# PLC-_-_-V3.net
KiCad netlist of a schematic drawn in Altium Designer
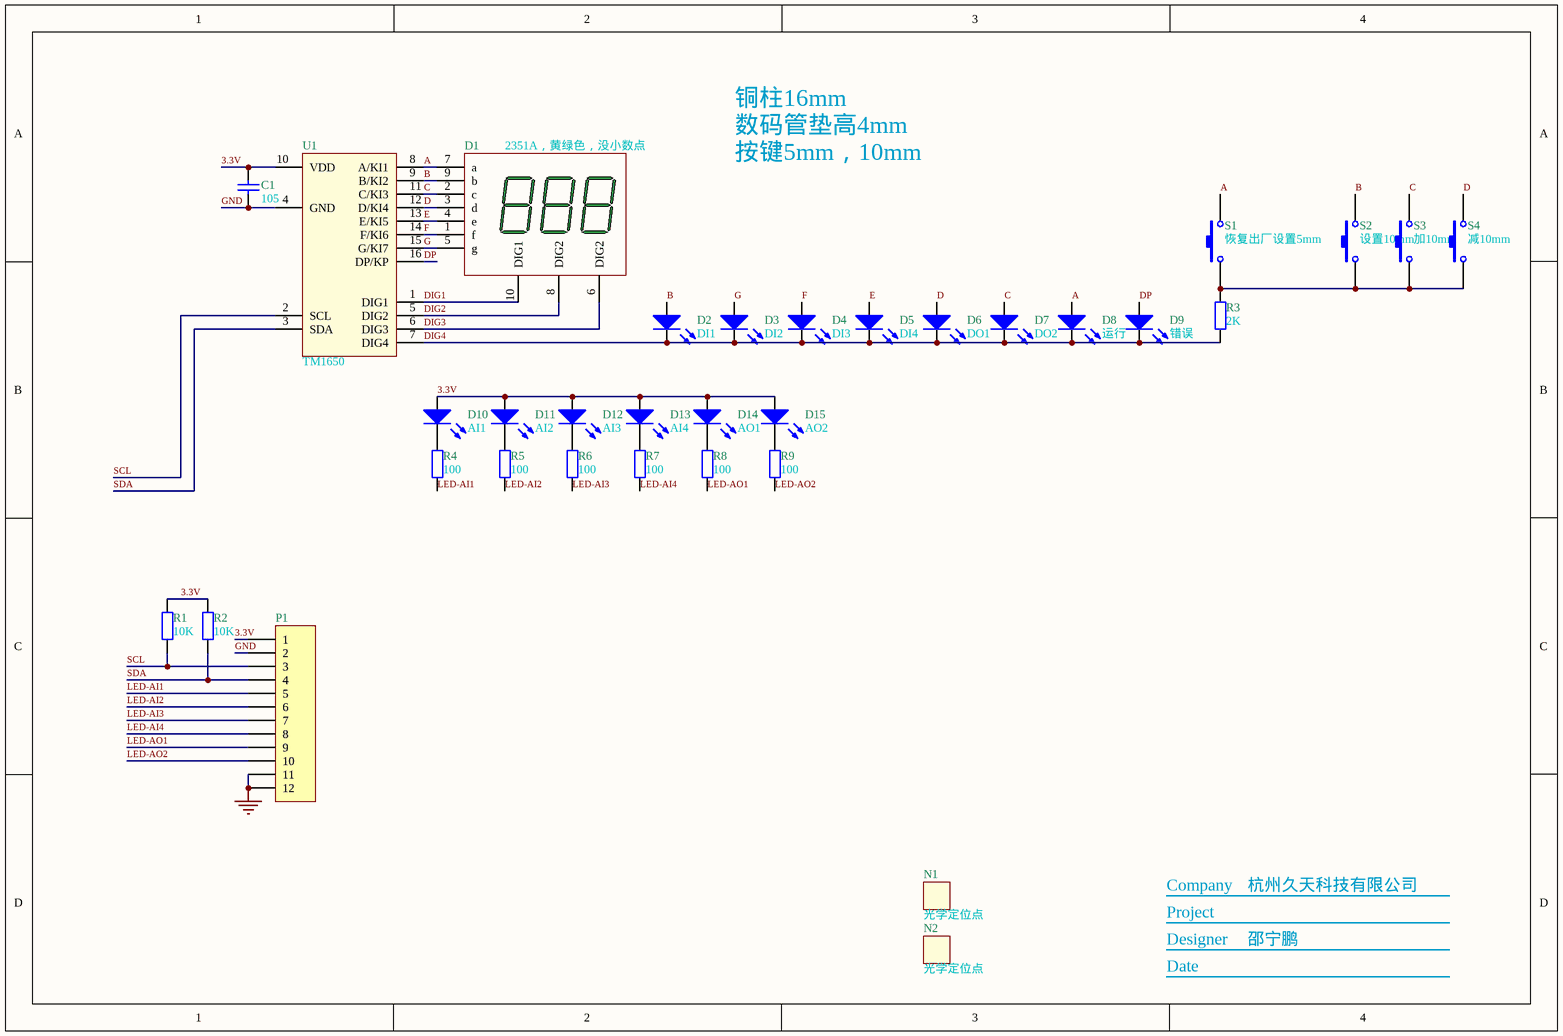
[diagram p0: PLC-无线通讯版-显示板-V3.SchDoc]

(export (version "E")
  (design (tool "Eeschema 10.0.6"))
  (components
    (comp (ref "C1")
      (value "105")
      (footprint "C-0603")
      (description "Capacitor")
      (fields (field (name "PUBLISHER") "Altium Limited"))
      (libsource (lib "元件2.0") (part "Cap"))
    )
    (comp (ref "D1")
      (value "2351A，黄绿色，没小数点")
      (footprint "3位0.25英寸")
      (libsource (lib "7显示屏-V1.0") (part "3位数码管-无点-2351A"))
    )
    (comp (ref "D2")
      (value "DI1")
      (footprint "LED-0603-GREEN")
      (fields (field (name "PUBLISHER") "Altium Limited"))
      (libsource (lib "4二极管-V1.1") (part "LED-0603-Blue"))
    )
    (comp (ref "D3")
      (value "DI2")
      (footprint "LED-0603-GREEN")
      (fields (field (name "PUBLISHER") "Altium Limited"))
      (libsource (lib "4二极管-V1.1") (part "LED-0603-Blue"))
    )
    (comp (ref "D4")
      (value "DI3")
      (footprint "LED-0603-GREEN")
      (fields (field (name "PUBLISHER") "Altium Limited"))
      (libsource (lib "4二极管-V1.1") (part "LED-0603-Blue"))
    )
    (comp (ref "D5")
      (value "DI4")
      (footprint "LED-0603-GREEN")
      (fields (field (name "PUBLISHER") "Altium Limited"))
      (libsource (lib "4二极管-V1.1") (part "LED-0603-Blue"))
    )
    (comp (ref "D6")
      (value "DO1")
      (footprint "LED-0603-GREEN")
      (fields (field (name "PUBLISHER") "Altium Limited"))
      (libsource (lib "4二极管-V1.1") (part "LED-0603-Blue"))
    )
    (comp (ref "D7")
      (value "DO2")
      (footprint "LED-0603-GREEN")
      (fields (field (name "PUBLISHER") "Altium Limited"))
      (libsource (lib "4二极管-V1.1") (part "LED-0603-Blue"))
    )
    (comp (ref "D8")
      (value "运行")
      (footprint "LED-0603-Blue")
      (fields (field (name "PUBLISHER") "Altium Limited"))
      (libsource (lib "4二极管-V1.1") (part "LED-0603-Blue"))
    )
    (comp (ref "D9")
      (value "错误")
      (footprint "LED-0603-Red")
      (fields (field (name "PUBLISHER") "Altium Limited"))
      (libsource (lib "4二极管-V1.1") (part "LED-0603-Blue"))
    )
    (comp (ref "D10")
      (value "AI1")
      (footprint "LED-0603-GREEN")
      (fields (field (name "PUBLISHER") "Altium Limited"))
      (libsource (lib "4二极管-V1.1") (part "LED-0603-Blue"))
    )
    (comp (ref "D11")
      (value "AI2")
      (footprint "LED-0603-GREEN")
      (fields (field (name "PUBLISHER") "Altium Limited"))
      (libsource (lib "4二极管-V1.1") (part "LED-0603-Blue"))
    )
    (comp (ref "D12")
      (value "AI3")
      (footprint "LED-0603-GREEN")
      (fields (field (name "PUBLISHER") "Altium Limited"))
      (libsource (lib "4二极管-V1.1") (part "LED-0603-Blue"))
    )
    (comp (ref "D13")
      (value "AI4")
      (footprint "LED-0603-GREEN")
      (fields (field (name "PUBLISHER") "Altium Limited"))
      (libsource (lib "4二极管-V1.1") (part "LED-0603-Blue"))
    )
    (comp (ref "D14")
      (value "AO1")
      (footprint "LED-0603-GREEN")
      (fields (field (name "PUBLISHER") "Altium Limited"))
      (libsource (lib "4二极管-V1.1") (part "LED-0603-Blue"))
    )
    (comp (ref "D15")
      (value "AO2")
      (footprint "LED-0603-GREEN")
      (fields (field (name "PUBLISHER") "Altium Limited"))
      (libsource (lib "4二极管-V1.1") (part "LED-0603-Blue"))
    )
    (comp (ref "N1") (value "光学定位点") (footprint "MARK-1mm-3mm") (libsource (lib "11其他元件-V1.0") (part "无引脚")))
    (comp (ref "N2") (value "光学定位点") (footprint "MARK-1mm-3mm") (libsource (lib "11其他元件-V1.0") (part "无引脚")))
    (comp (ref "P1")
      (value "~")
      (footprint "FPC-1.0mm下接翻盖_10P")
      (description "Header, 12-Pin")
      (fields (field (name "PUBLISHER") "Altium Limited"))
      (libsource (lib "5排针-V1.0") (part "Header 12"))
    )
    (comp (ref "R1")
      (value "10K")
      (footprint "R-0603")
      (description "0603")
      (fields (field (name "PUBLISHER") "Altium Limited"))
      (libsource (lib "") (part "Res2-0603_1"))
    )
    (comp (ref "R2")
      (value "10K")
      (footprint "R-0603")
      (description "0603")
      (fields (field (name "PUBLISHER") "Altium Limited"))
      (libsource (lib "") (part "Res2-0603_1"))
    )
    (comp (ref "R3")
      (value "2K")
      (footprint "R-0603")
      (description "0603")
      (fields (field (name "PUBLISHER") "Altium Limited"))
      (libsource (lib "1电阻-V1.0") (part "Res2-0603"))
    )
    (comp (ref "R4")
      (value "100")
      (footprint "R-0603")
      (description "0603")
      (fields (field (name "PUBLISHER") "Altium Limited"))
      (libsource (lib "1电阻-V1.0") (part "Res2-0603"))
    )
    (comp (ref "R5")
      (value "100")
      (footprint "R-0603")
      (description "0603")
      (fields (field (name "PUBLISHER") "Altium Limited"))
      (libsource (lib "1电阻-V1.0") (part "Res2-0603"))
    )
    (comp (ref "R6")
      (value "100")
      (footprint "R-0603")
      (description "0603")
      (fields (field (name "PUBLISHER") "Altium Limited"))
      (libsource (lib "1电阻-V1.0") (part "Res2-0603"))
    )
    (comp (ref "R7")
      (value "100")
      (footprint "R-0603")
      (description "0603")
      (fields (field (name "PUBLISHER") "Altium Limited"))
      (libsource (lib "1电阻-V1.0") (part "Res2-0603"))
    )
    (comp (ref "R8")
      (value "100")
      (footprint "R-0603")
      (description "0603")
      (fields (field (name "PUBLISHER") "Altium Limited"))
      (libsource (lib "1电阻-V1.0") (part "Res2-0603"))
    )
    (comp (ref "R9")
      (value "100")
      (footprint "R-0603")
      (description "0603")
      (fields (field (name "PUBLISHER") "Altium Limited"))
      (libsource (lib "1电阻-V1.0") (part "Res2-0603"))
    )
    (comp (ref "S1")
      (value "恢复出厂设置5mm")
      (footprint "SB-6*6*9.5_贴片")
      (description "SB-6*6*10")
      (fields (field (name "PUBLISHER") "Altium Limited"))
      (libsource (lib "开关-V1") (part "SB-6*6*9"))
    )
    (comp (ref "S2")
      (value "设置10mm")
      (footprint "SB-6*6*9.5_贴片")
      (description "SB-6*6*10")
      (fields (field (name "PUBLISHER") "Altium Limited"))
      (libsource (lib "开关-V1") (part "SB-6*6*9"))
    )
    (comp (ref "S3")
      (value "加10mm")
      (footprint "SB-6*6*9.5_贴片")
      (description "SB-6*6*10")
      (fields (field (name "PUBLISHER") "Altium Limited"))
      (libsource (lib "开关-V1") (part "SB-6*6*9"))
    )
    (comp (ref "S4")
      (value "减10mm")
      (footprint "SB-6*6*9.5_贴片")
      (description "SB-6*6*10")
      (fields (field (name "PUBLISHER") "Altium Limited"))
      (libsource (lib "开关-V1") (part "SB-6*6*9"))
    )
    (comp (ref "U1")
      (value "TM1650")
      (footprint "SOP-16-M")
      (description "共阴数码管驱动器")
      (libsource (lib "8集成电路-V1.1") (part "TM1650"))
    )
  )
  (nets
    (net (code "1") (name "/3.3V") (class "Default")
      (node (ref "C1") (pin "2") (pinfunction "2_2") (pintype "passive"))
      (node (ref "D10") (pin "1") (pinfunction "A_1") (pintype "passive"))
      (node (ref "D11") (pin "1") (pinfunction "A_1") (pintype "passive"))
      (node (ref "D12") (pin "1") (pinfunction "A_1") (pintype "passive"))
      (node (ref "D13") (pin "1") (pinfunction "A_1") (pintype "passive"))
      (node (ref "D14") (pin "1") (pinfunction "A_1") (pintype "passive"))
      (node (ref "D15") (pin "1") (pinfunction "A_1") (pintype "passive"))
      (node (ref "P1") (pin "1") (pinfunction "1_1") (pintype "passive"))
      (node (ref "R1") (pin "2") (pinfunction "2_2") (pintype "passive"))
      (node (ref "R2") (pin "2") (pinfunction "2_2") (pintype "passive"))
      (node (ref "U1") (pin "10") (pinfunction "VDD_10") (pintype "passive"))
    )
    (net (code "2") (name "/A") (class "Default")
      (node (ref "D1") (pin "7") (pinfunction "a_7") (pintype "passive"))
      (node (ref "D8") (pin "1") (pinfunction "A_1") (pintype "passive"))
      (node (ref "S1") (pin "2") (pinfunction "2_2") (pintype "passive"))
      (node (ref "U1") (pin "8") (pinfunction "A/KI1_8") (pintype "passive"))
    )
    (net (code "3") (name "/B") (class "Default")
      (node (ref "D1") (pin "9") (pinfunction "b_9") (pintype "passive"))
      (node (ref "D2") (pin "1") (pinfunction "A_1") (pintype "passive"))
      (node (ref "S2") (pin "2") (pinfunction "2_2") (pintype "passive"))
      (node (ref "U1") (pin "9") (pinfunction "B/KI2_9") (pintype "passive"))
    )
    (net (code "4") (name "/C") (class "Default")
      (node (ref "D1") (pin "2") (pinfunction "c_2") (pintype "passive"))
      (node (ref "D7") (pin "1") (pinfunction "A_1") (pintype "passive"))
      (node (ref "S3") (pin "2") (pinfunction "2_2") (pintype "passive"))
      (node (ref "U1") (pin "11") (pinfunction "C/KI3_11") (pintype "passive"))
    )
    (net (code "5") (name "/D") (class "Default")
      (node (ref "D1") (pin "3") (pinfunction "d_3") (pintype "passive"))
      (node (ref "D6") (pin "1") (pinfunction "A_1") (pintype "passive"))
      (node (ref "S4") (pin "2") (pinfunction "2_2") (pintype "passive"))
      (node (ref "U1") (pin "12") (pinfunction "D/KI4_12") (pintype "passive"))
    )
    (net (code "6") (name "/DIG1") (class "Default")
      (node (ref "D1") (pin "10") (pinfunction "DIG1_10") (pintype "passive"))
      (node (ref "U1") (pin "1") (pinfunction "DIG1_1") (pintype "passive"))
    )
    (net (code "7") (name "/DIG2") (class "Default")
      (node (ref "D1") (pin "8") (pinfunction "DIG2_8") (pintype "passive"))
      (node (ref "U1") (pin "5") (pinfunction "DIG2_5") (pintype "passive"))
    )
    (net (code "8") (name "/DIG3") (class "Default")
      (node (ref "D1") (pin "6") (pinfunction "DIG2_6") (pintype "passive"))
      (node (ref "U1") (pin "6") (pinfunction "DIG3_6") (pintype "passive"))
    )
    (net (code "9") (name "/DIG4") (class "Default")
      (node (ref "D2") (pin "2") (pinfunction "K_2") (pintype "passive"))
      (node (ref "D3") (pin "2") (pinfunction "K_2") (pintype "passive"))
      (node (ref "D4") (pin "2") (pinfunction "K_2") (pintype "passive"))
      (node (ref "D5") (pin "2") (pinfunction "K_2") (pintype "passive"))
      (node (ref "D6") (pin "2") (pinfunction "K_2") (pintype "passive"))
      (node (ref "D7") (pin "2") (pinfunction "K_2") (pintype "passive"))
      (node (ref "D8") (pin "2") (pinfunction "K_2") (pintype "passive"))
      (node (ref "D9") (pin "2") (pinfunction "K_2") (pintype "passive"))
      (node (ref "R3") (pin "2") (pinfunction "2_2") (pintype "passive"))
      (node (ref "U1") (pin "7") (pinfunction "DIG4_7") (pintype "passive"))
    )
    (net (code "10") (name "/DP") (class "Default")
      (node (ref "D9") (pin "1") (pinfunction "A_1") (pintype "passive"))
      (node (ref "U1") (pin "16") (pinfunction "DP/KP_16") (pintype "passive"))
    )
    (net (code "11") (name "/E") (class "Default")
      (node (ref "D1") (pin "4") (pinfunction "e_4") (pintype "passive"))
      (node (ref "D5") (pin "1") (pinfunction "A_1") (pintype "passive"))
      (node (ref "U1") (pin "13") (pinfunction "E/KI5_13") (pintype "passive"))
    )
    (net (code "12") (name "/F") (class "Default")
      (node (ref "D1") (pin "1") (pinfunction "f_1") (pintype "passive"))
      (node (ref "D4") (pin "1") (pinfunction "A_1") (pintype "passive"))
      (node (ref "U1") (pin "14") (pinfunction "F/KI6_14") (pintype "passive"))
    )
    (net (code "13") (name "/G") (class "Default")
      (node (ref "D1") (pin "5") (pinfunction "g_5") (pintype "passive"))
      (node (ref "D3") (pin "1") (pinfunction "A_1") (pintype "passive"))
      (node (ref "U1") (pin "15") (pinfunction "G/KI7_15") (pintype "passive"))
    )
    (net (code "14") (name "/LED-AI1") (class "Default")
      (node (ref "P1") (pin "5") (pinfunction "5_5") (pintype "passive"))
      (node (ref "R4") (pin "2") (pinfunction "2_2") (pintype "passive"))
    )
    (net (code "15") (name "/LED-AI2") (class "Default")
      (node (ref "P1") (pin "6") (pinfunction "6_6") (pintype "passive"))
      (node (ref "R5") (pin "2") (pinfunction "2_2") (pintype "passive"))
    )
    (net (code "16") (name "/LED-AI3") (class "Default")
      (node (ref "P1") (pin "7") (pinfunction "7_7") (pintype "passive"))
      (node (ref "R6") (pin "2") (pinfunction "2_2") (pintype "passive"))
    )
    (net (code "17") (name "/LED-AI4") (class "Default")
      (node (ref "P1") (pin "8") (pinfunction "8_8") (pintype "passive"))
      (node (ref "R7") (pin "2") (pinfunction "2_2") (pintype "passive"))
    )
    (net (code "18") (name "/LED-AO1") (class "Default")
      (node (ref "P1") (pin "9") (pinfunction "9_9") (pintype "passive"))
      (node (ref "R8") (pin "2") (pinfunction "2_2") (pintype "passive"))
    )
    (net (code "19") (name "/LED-AO2") (class "Default")
      (node (ref "P1") (pin "10") (pinfunction "10_10") (pintype "passive"))
      (node (ref "R9") (pin "2") (pinfunction "2_2") (pintype "passive"))
    )
    (net (code "20") (name "/SCL") (class "Default")
      (node (ref "P1") (pin "3") (pinfunction "3_3") (pintype "passive"))
      (node (ref "R1") (pin "1") (pinfunction "1_1") (pintype "passive"))
      (node (ref "U1") (pin "2") (pinfunction "SCL_2") (pintype "passive"))
    )
    (net (code "21") (name "/SDA") (class "Default")
      (node (ref "P1") (pin "4") (pinfunction "4_4") (pintype "passive"))
      (node (ref "R2") (pin "1") (pinfunction "1_1") (pintype "passive"))
      (node (ref "U1") (pin "3") (pinfunction "SDA_3") (pintype "passive"))
    )
    (net (code "22") (name "GND") (class "Default")
      (node (ref "C1") (pin "1") (pinfunction "1_1") (pintype "passive"))
      (node (ref "P1") (pin "11") (pinfunction "11_11") (pintype "passive"))
      (node (ref "P1") (pin "12") (pinfunction "12_12") (pintype "passive"))
      (node (ref "P1") (pin "2") (pinfunction "2_2") (pintype "passive"))
      (node (ref "U1") (pin "4") (pinfunction "GND_4") (pintype "passive"))
    )
    (net (code "23") (name "Net-(D10-K)") (class "Default")
      (node (ref "D10") (pin "2") (pinfunction "K_2") (pintype "passive"))
      (node (ref "R4") (pin "1") (pinfunction "1_1") (pintype "passive"))
    )
    (net (code "24") (name "Net-(D11-K)") (class "Default")
      (node (ref "D11") (pin "2") (pinfunction "K_2") (pintype "passive"))
      (node (ref "R5") (pin "1") (pinfunction "1_1") (pintype "passive"))
    )
    (net (code "25") (name "Net-(D12-K)") (class "Default")
      (node (ref "D12") (pin "2") (pinfunction "K_2") (pintype "passive"))
      (node (ref "R6") (pin "1") (pinfunction "1_1") (pintype "passive"))
    )
    (net (code "26") (name "Net-(D13-K)") (class "Default")
      (node (ref "D13") (pin "2") (pinfunction "K_2") (pintype "passive"))
      (node (ref "R7") (pin "1") (pinfunction "1_1") (pintype "passive"))
    )
    (net (code "27") (name "Net-(D14-K)") (class "Default")
      (node (ref "D14") (pin "2") (pinfunction "K_2") (pintype "passive"))
      (node (ref "R8") (pin "1") (pinfunction "1_1") (pintype "passive"))
    )
    (net (code "28") (name "Net-(D15-K)") (class "Default")
      (node (ref "D15") (pin "2") (pinfunction "K_2") (pintype "passive"))
      (node (ref "R9") (pin "1") (pinfunction "1_1") (pintype "passive"))
    )
    (net (code "29") (name "Net-(R3-Pad1)") (class "Default")
      (node (ref "R3") (pin "1") (pinfunction "1_1") (pintype "passive"))
      (node (ref "S1") (pin "1") (pinfunction "1_1") (pintype "passive"))
      (node (ref "S2") (pin "1") (pinfunction "1_1") (pintype "passive"))
      (node (ref "S3") (pin "1") (pinfunction "1_1") (pintype "passive"))
      (node (ref "S4") (pin "1") (pinfunction "1_1") (pintype "passive"))
    )
  )
)
